# LCD_Camera_Connectors.net
KiCad netlist of a schematic drawn in Altium Designer
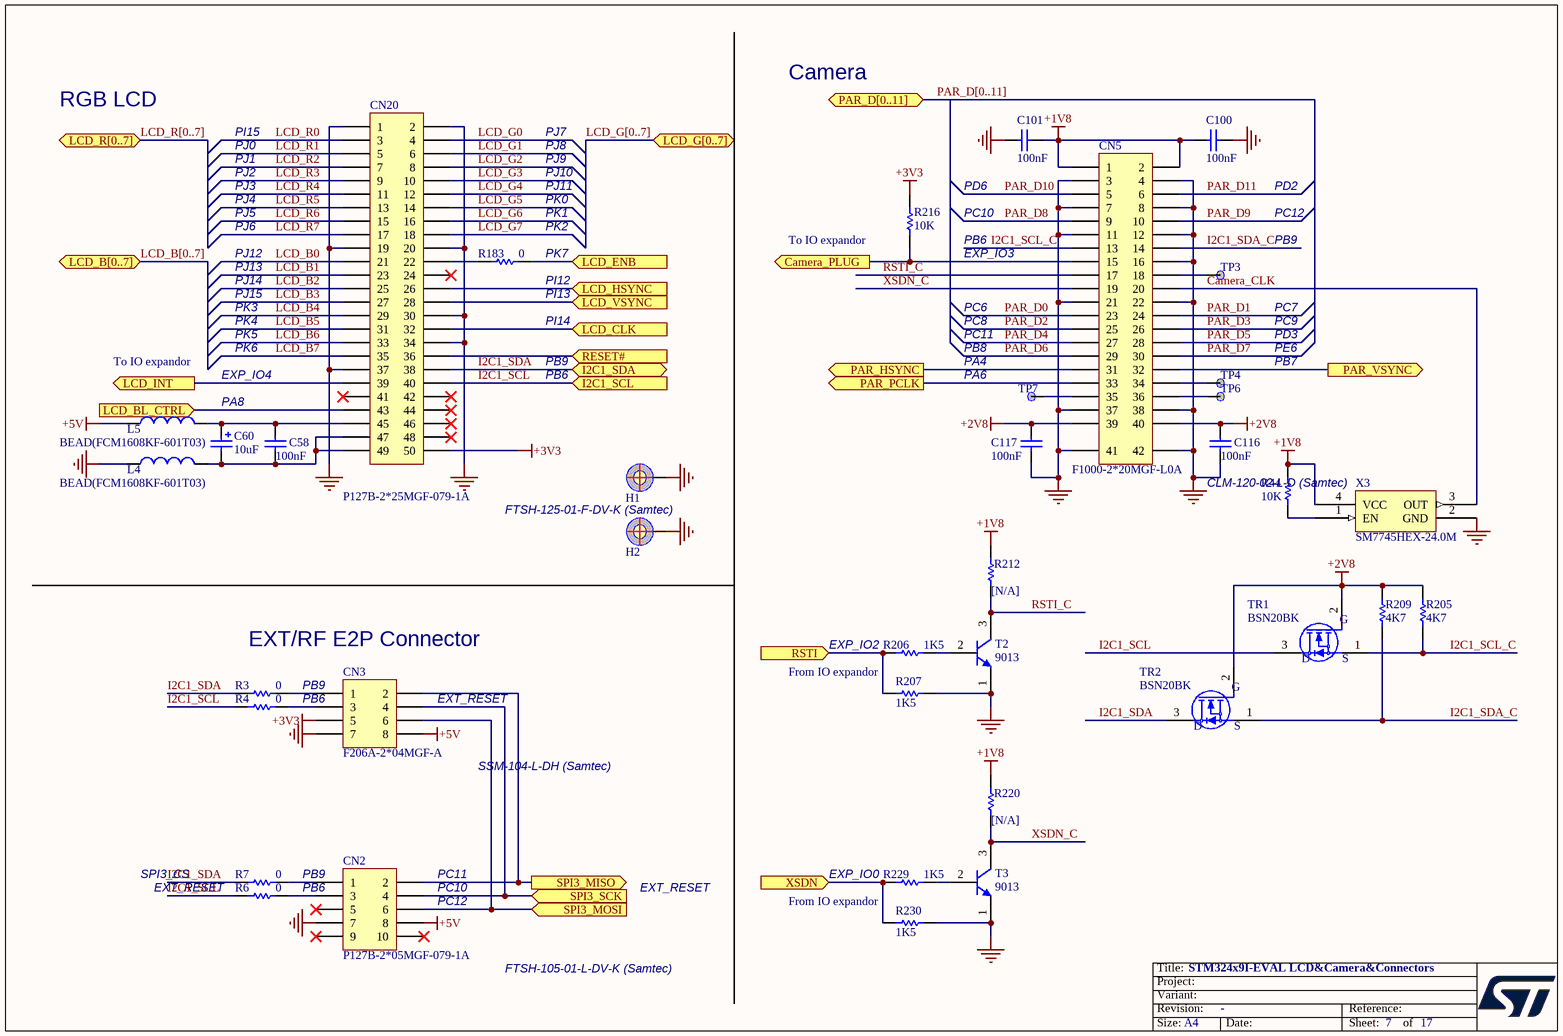
[diagram p0: LCD&Camera&Connectors.SchDoc]

(export (version "E")
  (design (tool "Eeschema 10.0.6"))
  (components
    (comp (ref "C58")
      (value "100nF")
      (footprint "0603C")
      (description "Capacitor")
      (fields (field (name "PUBLISHER") "Altium Limited"))
      (libsource (lib "Miscellaneous Devices") (part "Cap"))
    )
    (comp (ref "C60")
      (value "10uF")
      (footprint "TAN-A")
      (description "Polarized Capacitor (Radial)")
      (fields (field (name "PUBLISHER") "Altium Limited"))
      (libsource (lib "Miscellaneous Devices") (part "Cap Pol1"))
    )
    (comp (ref "C100")
      (value "100nF")
      (footprint "0603C")
      (description "Capacitor")
      (fields (field (name "PUBLISHER") "Altium Limited"))
      (libsource (lib "Miscellaneous Devices") (part "Cap"))
    )
    (comp (ref "C101")
      (value "100nF")
      (footprint "0603C")
      (description "Capacitor")
      (fields (field (name "PUBLISHER") "Altium Limited"))
      (libsource (lib "Miscellaneous Devices") (part "Cap"))
    )
    (comp (ref "C116")
      (value "100nF")
      (footprint "0603C")
      (description "Capacitor")
      (fields (field (name "PUBLISHER") "Altium Limited"))
      (libsource (lib "Miscellaneous Devices") (part "Cap"))
    )
    (comp (ref "C117")
      (value "100nF")
      (footprint "0603C")
      (description "Capacitor")
      (fields (field (name "PUBLISHER") "Altium Limited"))
      (libsource (lib "Miscellaneous Devices") (part "Cap"))
    )
    (comp (ref "CN2")
      (value "P127B-2*05MGF-079-1A")
      (footprint "FTSH-105-01-L-DV-K")
      (description "Header, 5-Pin, Dual row")
      (fields (field (name "PUBLISHER") "Altium Limited"))
      (libsource (lib "mb1045") (part "FTSH-15-01-L-DV-ES-K"))
    )
    (comp (ref "CN3")
      (value "F206A-2*04MGF-A")
      (footprint "SSM-104-L-DH")
      (description "Header, 5-Pin, Dual row")
      (fields (field (name "PUBLISHER") "Altium Limited"))
      (libsource (lib "mb1045") (part "SSM-104-L-DH"))
    )
    (comp (ref "CN5")
      (value "F1000-2*20MGF-L0A")
      (footprint "CLM-120-02-L-D")
      (description "Header, 20-Pin, Dual row")
      (fields (field (name "PUBLISHER") "Altium Limited"))
      (libsource (lib "mb1045") (part "CLM-120-02-L-D"))
    )
    (comp (ref "CN20")
      (value "P127B-2*25MGF-079-1A")
      (footprint "FTSH-125-01-F-DV")
      (description "Header, 26-Pin, Dual row")
      (fields (field (name "PUBLISHER") "Altium Limited"))
      (libsource (lib "mb1045") (part "Header 25X2"))
    )
    (comp (ref "H1")
      (value "POSITION HOLE")
      (footprint "HOLE_C9D4R5")
      (libsource (lib "mb1045") (part "POSITION HOLE"))
    )
    (comp (ref "H2")
      (value "POSITION HOLE")
      (footprint "HOLE_C9D4R5")
      (libsource (lib "mb1045") (part "POSITION HOLE"))
    )
    (comp (ref "L4")
      (value "BEAD(FCM1608KF-601T03)")
      (footprint "0603L")
      (description "Inductor")
      (fields (field (name "PUBLISHER") "Altium Limited"))
      (libsource (lib "Miscellaneous Devices") (part "Inductor"))
    )
    (comp (ref "L5")
      (value "BEAD(FCM1608KF-601T03)")
      (footprint "0603L")
      (description "Inductor")
      (fields (field (name "PUBLISHER") "Altium Limited"))
      (libsource (lib "Miscellaneous Devices") (part "Inductor"))
    )
    (comp (ref "R3")
      (value "0")
      (footprint "0603R")
      (description "Resistor")
      (fields (field (name "PUBLISHER") "Altium Limited"))
      (libsource (lib "Miscellaneous Devices") (part "Res1"))
    )
    (comp (ref "R4")
      (value "0")
      (footprint "0603R")
      (description "Resistor")
      (fields (field (name "PUBLISHER") "Altium Limited"))
      (libsource (lib "Miscellaneous Devices") (part "Res1"))
    )
    (comp (ref "R6")
      (value "0")
      (footprint "0603R")
      (description "Resistor")
      (fields (field (name "PUBLISHER") "Altium Limited"))
      (libsource (lib "Miscellaneous Devices") (part "Res1"))
    )
    (comp (ref "R7")
      (value "0")
      (footprint "0603R")
      (description "Resistor")
      (fields (field (name "PUBLISHER") "Altium Limited"))
      (libsource (lib "Miscellaneous Devices") (part "Res1"))
    )
    (comp (ref "R44")
      (value "10K")
      (footprint "0402R")
      (description "Resistor")
      (fields (field (name "PUBLISHER") "Altium Limited"))
      (libsource (lib "Miscellaneous Devices") (part "Res1"))
    )
    (comp (ref "R183")
      (value "0")
      (footprint "0603R")
      (description "Resistor")
      (fields (field (name "PUBLISHER") "Altium Limited"))
      (libsource (lib "Miscellaneous Devices") (part "Res1"))
    )
    (comp (ref "R205")
      (value "4K7")
      (footprint "0603R")
      (description "Resistor")
      (fields (field (name "PUBLISHER") "Altium Limited"))
      (libsource (lib "Miscellaneous Devices") (part "res1"))
    )
    (comp (ref "R206")
      (value "1K5")
      (footprint "0603R")
      (description "Resistor")
      (fields (field (name "PUBLISHER") "Altium Limited"))
      (libsource (lib "Miscellaneous Devices") (part "Res1"))
    )
    (comp (ref "R207")
      (value "1K5")
      (footprint "0603R")
      (description "Resistor")
      (fields (field (name "PUBLISHER") "Altium Limited"))
      (libsource (lib "Miscellaneous Devices") (part "Res1"))
    )
    (comp (ref "R209")
      (value "4K7")
      (footprint "0603R")
      (description "Resistor")
      (fields (field (name "PUBLISHER") "Altium Limited"))
      (libsource (lib "Miscellaneous Devices") (part "res1"))
    )
    (comp (ref "R212")
      (value "[N/A]")
      (footprint "0603R")
      (description "Resistor")
      (fields (field (name "PUBLISHER") "Altium Limited"))
      (libsource (lib "Miscellaneous Devices") (part "res1"))
    )
    (comp (ref "R216")
      (value "10K")
      (footprint "0603R")
      (description "Resistor")
      (fields (field (name "PUBLISHER") "Altium Limited"))
      (libsource (lib "Miscellaneous Devices") (part "Res1"))
    )
    (comp (ref "R220")
      (value "[N/A]")
      (footprint "0603R")
      (description "Resistor")
      (fields (field (name "PUBLISHER") "Altium Limited"))
      (libsource (lib "Miscellaneous Devices") (part "res1"))
    )
    (comp (ref "R229")
      (value "1K5")
      (footprint "0603R")
      (description "Resistor")
      (fields (field (name "PUBLISHER") "Altium Limited"))
      (libsource (lib "Miscellaneous Devices") (part "Res1"))
    )
    (comp (ref "R230")
      (value "1K5")
      (footprint "0603R")
      (description "Resistor")
      (fields (field (name "PUBLISHER") "Altium Limited"))
      (libsource (lib "Miscellaneous Devices") (part "Res1"))
    )
    (comp (ref "T2")
      (value "9013")
      (footprint "SOT23-213")
      (description "NPN Bipolar Transistor")
      (fields (field (name "PUBLISHER") "Altium Limited"))
      (libsource (lib "mb1045") (part "NPN"))
    )
    (comp (ref "T3")
      (value "9013")
      (footprint "SOT23-213")
      (description "NPN Bipolar Transistor")
      (fields (field (name "PUBLISHER") "Altium Limited"))
      (libsource (lib "mb1045") (part "NPN"))
    )
    (comp (ref "TP3") (value "~") (footprint "TP") (libsource (lib "*") (part "TP")))
    (comp (ref "TP4") (value "~") (footprint "TP") (libsource (lib "*") (part "TP")))
    (comp (ref "TP6") (value "~") (footprint "TP") (libsource (lib "*") (part "TP")))
    (comp (ref "TP7") (value "~") (footprint "TP") (libsource (lib "*") (part "TP")))
    (comp (ref "TR1")
      (value "BSN20BK")
      (footprint "SOT23-213")
      (description "Transistor, N-channel enhancement mode field-effect transistor")
      (libsource (lib "MB525") (part "2N7000"))
    )
    (comp (ref "TR2")
      (value "BSN20BK")
      (footprint "SOT23-213")
      (description "Transistor, N-channel enhancement mode field-effect transistor")
      (libsource (lib "MB525") (part "2N7000"))
    )
    (comp (ref "X3")
      (value "SM7745HEX-24.0M")
      (footprint "OSC_4SM_7X5")
      (libsource (lib "MB784") (part "SM7745HEV-50.0M"))
    )
  )
  (nets
    (net (code "1") (name "+1V8") (class "Default")
      (node (ref "C100") (pin "1") (pinfunction "1_1") (pintype "passive"))
      (node (ref "C101") (pin "2") (pinfunction "2_2") (pintype "passive"))
      (node (ref "CN5") (pin "1") (pinfunction "1_1") (pintype "passive"))
      (node (ref "CN5") (pin "2") (pinfunction "2_2") (pintype "passive"))
      (node (ref "R212") (pin "2") (pinfunction "2_2") (pintype "passive"))
      (node (ref "R220") (pin "2") (pinfunction "2_2") (pintype "passive"))
      (node (ref "R44") (pin "2") (pinfunction "2_2") (pintype "passive"))
      (node (ref "X3") (pin "4") (pinfunction "VCC_4") (pintype "passive"))
    )
    (net (code "2") (name "+2V8") (class "Default")
      (node (ref "C116") (pin "1") (pinfunction "1_1") (pintype "passive"))
      (node (ref "C117") (pin "1") (pinfunction "1_1") (pintype "passive"))
      (node (ref "CN5") (pin "39") (pinfunction "39_39") (pintype "passive"))
      (node (ref "CN5") (pin "40") (pinfunction "40_40") (pintype "passive"))
      (node (ref "R205") (pin "2") (pinfunction "2_2") (pintype "passive"))
      (node (ref "R209") (pin "2") (pinfunction "2_2") (pintype "passive"))
      (node (ref "TR1") (pin "2") (pinfunction "G_2") (pintype "passive"))
      (node (ref "TR2") (pin "2") (pinfunction "G_2") (pintype "passive"))
    )
    (net (code "3") (name "+3V3") (class "Default")
      (node (ref "CN20") (pin "50") (pinfunction "50_50") (pintype "passive"))
      (node (ref "CN3") (pin "5") (pinfunction "5_5") (pintype "passive"))
      (node (ref "R216") (pin "1") (pinfunction "1_1") (pintype "passive"))
    )
    (net (code "4") (name "+5V") (class "Default")
      (node (ref "CN2") (pin "8") (pinfunction "8_8") (pintype "passive"))
      (node (ref "CN3") (pin "8") (pinfunction "8_8") (pintype "passive"))
      (node (ref "L5") (pin "1") (pinfunction "1_1") (pintype "passive"))
    )
    (net (code "5") (name "/Camera_CLK") (class "Default")
      (node (ref "CN5") (pin "20") (pinfunction "20_20") (pintype "passive"))
      (node (ref "X3") (pin "3") (pinfunction "OUT_3") (pintype "output"))
    )
    (net (code "6") (name "/Camera_PLUG") (class "Default")
      (node (ref "CN5") (pin "15") (pinfunction "15_15") (pintype "passive"))
      (node (ref "R216") (pin "2") (pinfunction "2_2") (pintype "passive"))
    )
    (net (code "7") (name "/I2C1_SCL") (class "Default")
      (node (ref "CN20") (pin "40") (pinfunction "40_40") (pintype "passive"))
      (node (ref "R4") (pin "1") (pinfunction "1_1") (pintype "passive"))
      (node (ref "R6") (pin "1") (pinfunction "1_1") (pintype "passive"))
      (node (ref "TR1") (pin "3") (pinfunction "D_3") (pintype "passive"))
    )
    (net (code "8") (name "/I2C1_SCL_C") (class "Default")
      (node (ref "CN5") (pin "13") (pinfunction "13_13") (pintype "passive"))
      (node (ref "R205") (pin "1") (pinfunction "1_1") (pintype "passive"))
      (node (ref "TR1") (pin "1") (pinfunction "S_1") (pintype "passive"))
    )
    (net (code "9") (name "/I2C1_SDA") (class "Default")
      (node (ref "CN20") (pin "38") (pinfunction "38_38") (pintype "passive"))
      (node (ref "R3") (pin "1") (pinfunction "1_1") (pintype "passive"))
      (node (ref "R7") (pin "1") (pinfunction "1_1") (pintype "passive"))
      (node (ref "TR2") (pin "3") (pinfunction "D_3") (pintype "passive"))
    )
    (net (code "10") (name "/I2C1_SDA_C") (class "Default")
      (node (ref "CN5") (pin "14") (pinfunction "14_14") (pintype "passive"))
      (node (ref "R209") (pin "1") (pinfunction "1_1") (pintype "passive"))
      (node (ref "TR2") (pin "1") (pinfunction "S_1") (pintype "passive"))
    )
    (net (code "11") (name "/LCD_B0") (class "Default")
      (node (ref "CN20") (pin "21") (pinfunction "21_21") (pintype "passive"))
    )
    (net (code "12") (name "/LCD_B1") (class "Default")
      (node (ref "CN20") (pin "23") (pinfunction "23_23") (pintype "passive"))
    )
    (net (code "13") (name "/LCD_B2") (class "Default")
      (node (ref "CN20") (pin "25") (pinfunction "25_25") (pintype "passive"))
    )
    (net (code "14") (name "/LCD_B3") (class "Default")
      (node (ref "CN20") (pin "27") (pinfunction "27_27") (pintype "passive"))
    )
    (net (code "15") (name "/LCD_B4") (class "Default")
      (node (ref "CN20") (pin "29") (pinfunction "29_29") (pintype "passive"))
    )
    (net (code "16") (name "/LCD_B5") (class "Default")
      (node (ref "CN20") (pin "31") (pinfunction "31_31") (pintype "passive"))
    )
    (net (code "17") (name "/LCD_B6") (class "Default")
      (node (ref "CN20") (pin "33") (pinfunction "33_33") (pintype "passive"))
    )
    (net (code "18") (name "/LCD_B7") (class "Default")
      (node (ref "CN20") (pin "35") (pinfunction "35_35") (pintype "passive"))
    )
    (net (code "19") (name "/LCD_BL_CTRL") (class "Default")
      (node (ref "CN20") (pin "43") (pinfunction "43_43") (pintype "passive"))
    )
    (net (code "21") (name "/LCD_CLK") (class "Default")
      (node (ref "CN20") (pin "32") (pinfunction "32_32") (pintype "passive"))
    )
    (net (code "22") (name "/LCD_ENB") (class "Default")
      (node (ref "R183") (pin "2") (pinfunction "2_2") (pintype "passive"))
    )
    (net (code "23") (name "/LCD_G0") (class "Default")
      (node (ref "CN20") (pin "4") (pinfunction "4_4") (pintype "passive"))
    )
    (net (code "24") (name "/LCD_G1") (class "Default")
      (node (ref "CN20") (pin "6") (pinfunction "6_6") (pintype "passive"))
    )
    (net (code "25") (name "/LCD_G2") (class "Default")
      (node (ref "CN20") (pin "8") (pinfunction "8_8") (pintype "passive"))
    )
    (net (code "26") (name "/LCD_G3") (class "Default")
      (node (ref "CN20") (pin "10") (pinfunction "10_10") (pintype "passive"))
    )
    (net (code "27") (name "/LCD_G4") (class "Default")
      (node (ref "CN20") (pin "12") (pinfunction "12_12") (pintype "passive"))
    )
    (net (code "28") (name "/LCD_G5") (class "Default")
      (node (ref "CN20") (pin "14") (pinfunction "14_14") (pintype "passive"))
    )
    (net (code "29") (name "/LCD_G6") (class "Default")
      (node (ref "CN20") (pin "16") (pinfunction "16_16") (pintype "passive"))
    )
    (net (code "30") (name "/LCD_G7") (class "Default")
      (node (ref "CN20") (pin "18") (pinfunction "18_18") (pintype "passive"))
    )
    (net (code "32") (name "/LCD_HSYNC") (class "Default")
      (node (ref "CN20") (pin "26") (pinfunction "26_26") (pintype "passive"))
    )
    (net (code "33") (name "/LCD_INT") (class "Default")
      (node (ref "CN20") (pin "39") (pinfunction "39_39") (pintype "passive"))
    )
    (net (code "34") (name "/LCD_R0") (class "Default")
      (node (ref "CN20") (pin "3") (pinfunction "3_3") (pintype "passive"))
    )
    (net (code "35") (name "/LCD_R1") (class "Default")
      (node (ref "CN20") (pin "5") (pinfunction "5_5") (pintype "passive"))
    )
    (net (code "36") (name "/LCD_R2") (class "Default")
      (node (ref "CN20") (pin "7") (pinfunction "7_7") (pintype "passive"))
    )
    (net (code "37") (name "/LCD_R3") (class "Default")
      (node (ref "CN20") (pin "9") (pinfunction "9_9") (pintype "passive"))
    )
    (net (code "38") (name "/LCD_R4") (class "Default")
      (node (ref "CN20") (pin "11") (pinfunction "11_11") (pintype "passive"))
    )
    (net (code "39") (name "/LCD_R5") (class "Default")
      (node (ref "CN20") (pin "13") (pinfunction "13_13") (pintype "passive"))
    )
    (net (code "40") (name "/LCD_R6") (class "Default")
      (node (ref "CN20") (pin "15") (pinfunction "15_15") (pintype "passive"))
    )
    (net (code "41") (name "/LCD_R7") (class "Default")
      (node (ref "CN20") (pin "17") (pinfunction "17_17") (pintype "passive"))
    )
    (net (code "43") (name "/LCD_VSYNC") (class "Default")
      (node (ref "CN20") (pin "28") (pinfunction "28_28") (pintype "passive"))
    )
    (net (code "44") (name "/PAR_D0") (class "Default")
      (node (ref "CN5") (pin "23") (pinfunction "23_23") (pintype "passive"))
    )
    (net (code "45") (name "/PAR_D1") (class "Default")
      (node (ref "CN5") (pin "24") (pinfunction "24_24") (pintype "passive"))
    )
    (net (code "46") (name "/PAR_D2") (class "Default")
      (node (ref "CN5") (pin "25") (pinfunction "25_25") (pintype "passive"))
    )
    (net (code "47") (name "/PAR_D3") (class "Default")
      (node (ref "CN5") (pin "26") (pinfunction "26_26") (pintype "passive"))
    )
    (net (code "48") (name "/PAR_D4") (class "Default")
      (node (ref "CN5") (pin "27") (pinfunction "27_27") (pintype "passive"))
    )
    (net (code "49") (name "/PAR_D5") (class "Default")
      (node (ref "CN5") (pin "28") (pinfunction "28_28") (pintype "passive"))
    )
    (net (code "50") (name "/PAR_D6") (class "Default")
      (node (ref "CN5") (pin "29") (pinfunction "29_29") (pintype "passive"))
    )
    (net (code "51") (name "/PAR_D7") (class "Default")
      (node (ref "CN5") (pin "30") (pinfunction "30_30") (pintype "passive"))
    )
    (net (code "52") (name "/PAR_D8") (class "Default")
      (node (ref "CN5") (pin "9") (pinfunction "9_9") (pintype "passive"))
    )
    (net (code "53") (name "/PAR_D9") (class "Default")
      (node (ref "CN5") (pin "10") (pinfunction "10_10") (pintype "passive"))
    )
    (net (code "54") (name "/PAR_D10") (class "Default")
      (node (ref "CN5") (pin "5") (pinfunction "5_5") (pintype "passive"))
    )
    (net (code "55") (name "/PAR_D11") (class "Default")
      (node (ref "CN5") (pin "6") (pinfunction "6_6") (pintype "passive"))
    )
    (net (code "57") (name "/PAR_HSYNC") (class "Default")
      (node (ref "CN5") (pin "31") (pinfunction "31_31") (pintype "passive"))
    )
    (net (code "58") (name "/PAR_PCLK") (class "Default")
      (node (ref "CN5") (pin "33") (pinfunction "33_33") (pintype "passive"))
    )
    (net (code "59") (name "/PAR_VSYNC") (class "Default")
      (node (ref "CN5") (pin "32") (pinfunction "32_32") (pintype "passive"))
    )
    (net (code "60") (name "/RESET#") (class "Default")
      (node (ref "CN20") (pin "36") (pinfunction "36_36") (pintype "passive"))
    )
    (net (code "61") (name "/RSTI") (class "Default")
      (node (ref "R206") (pin "2") (pinfunction "2_2") (pintype "passive"))
      (node (ref "R207") (pin "1") (pinfunction "1_1") (pintype "passive"))
    )
    (net (code "62") (name "/RSTI_C") (class "Default")
      (node (ref "CN5") (pin "17") (pinfunction "17_17") (pintype "passive"))
      (node (ref "R212") (pin "1") (pinfunction "1_1") (pintype "passive"))
      (node (ref "T2") (pin "3") (pinfunction "C_3") (pintype "passive"))
    )
    (net (code "63") (name "/SPI3_MISO") (class "Default")
      (node (ref "CN2") (pin "2") (pinfunction "2_2") (pintype "passive"))
      (node (ref "CN3") (pin "2") (pinfunction "2_2") (pintype "passive"))
    )
    (net (code "64") (name "/SPI3_MOSI") (class "Default")
      (node (ref "CN2") (pin "6") (pinfunction "6_6") (pintype "passive"))
      (node (ref "CN3") (pin "6") (pinfunction "6_6") (pintype "passive"))
    )
    (net (code "65") (name "/SPI3_SCK") (class "Default")
      (node (ref "CN2") (pin "4") (pinfunction "4_4") (pintype "passive"))
      (node (ref "CN3") (pin "4") (pinfunction "4_4") (pintype "passive"))
    )
    (net (code "66") (name "/XSDN") (class "Default")
      (node (ref "R229") (pin "2") (pinfunction "2_2") (pintype "passive"))
      (node (ref "R230") (pin "1") (pinfunction "1_1") (pintype "passive"))
    )
    (net (code "67") (name "/XSDN_C") (class "Default")
      (node (ref "CN5") (pin "19") (pinfunction "19_19") (pintype "passive"))
      (node (ref "R220") (pin "1") (pinfunction "1_1") (pintype "passive"))
      (node (ref "T3") (pin "3") (pinfunction "C_3") (pintype "passive"))
    )
    (net (code "68") (name "GND") (class "Default")
      (node (ref "C100") (pin "2") (pinfunction "2_2") (pintype "passive"))
      (node (ref "C101") (pin "1") (pinfunction "1_1") (pintype "passive"))
      (node (ref "C116") (pin "2") (pinfunction "2_2") (pintype "passive"))
      (node (ref "C117") (pin "2") (pinfunction "2_2") (pintype "passive"))
      (node (ref "CN2") (pin "7") (pinfunction "7_7") (pintype "passive"))
      (node (ref "CN20") (pin "1") (pinfunction "1_1") (pintype "passive"))
      (node (ref "CN20") (pin "19") (pinfunction "19_19") (pintype "passive"))
      (node (ref "CN20") (pin "2") (pinfunction "2_2") (pintype "passive"))
      (node (ref "CN20") (pin "20") (pinfunction "20_20") (pintype "passive"))
      (node (ref "CN20") (pin "30") (pinfunction "30_30") (pintype "passive"))
      (node (ref "CN20") (pin "34") (pinfunction "34_34") (pintype "passive"))
      (node (ref "CN20") (pin "37") (pinfunction "37_37") (pintype "passive"))
      (node (ref "CN3") (pin "7") (pinfunction "7_7") (pintype "passive"))
      (node (ref "CN5") (pin "11") (pinfunction "11_11") (pintype "passive"))
      (node (ref "CN5") (pin "12") (pinfunction "12_12") (pintype "passive"))
      (node (ref "CN5") (pin "16") (pinfunction "16_16") (pintype "passive"))
      (node (ref "CN5") (pin "21") (pinfunction "21_21") (pintype "passive"))
      (node (ref "CN5") (pin "22") (pinfunction "22_22") (pintype "passive"))
      (node (ref "CN5") (pin "3") (pinfunction "3_3") (pintype "passive"))
      (node (ref "CN5") (pin "37") (pinfunction "37_37") (pintype "passive"))
      (node (ref "CN5") (pin "38") (pinfunction "38_38") (pintype "passive"))
      (node (ref "CN5") (pin "4") (pinfunction "4_4") (pintype "passive"))
      (node (ref "CN5") (pin "41") (pinfunction "41_41") (pintype "passive"))
      (node (ref "CN5") (pin "42") (pinfunction "42_42") (pintype "passive"))
      (node (ref "CN5") (pin "7") (pinfunction "7_7") (pintype "passive"))
      (node (ref "CN5") (pin "8") (pinfunction "8_8") (pintype "passive"))
      (node (ref "H1") (pin "1") (pinfunction "1_1") (pintype "passive"))
      (node (ref "H2") (pin "1") (pinfunction "1_1") (pintype "passive"))
      (node (ref "L4") (pin "1") (pinfunction "1_1") (pintype "passive"))
      (node (ref "R207") (pin "2") (pinfunction "2_2") (pintype "passive"))
      (node (ref "R230") (pin "2") (pinfunction "2_2") (pintype "passive"))
      (node (ref "T2") (pin "1") (pinfunction "E_1") (pintype "passive"))
      (node (ref "T3") (pin "1") (pinfunction "E_1") (pintype "passive"))
      (node (ref "X3") (pin "2") (pinfunction "GND_2") (pintype "passive"))
    )
    (net (code "69") (name "Net-(C58-Pad1)") (class "Default")
      (node (ref "C58") (pin "1") (pinfunction "1_1") (pintype "passive"))
      (node (ref "C60") (pin "1") (pinfunction "1_1") (pintype "passive"))
      (node (ref "CN20") (pin "45") (pinfunction "45_45") (pintype "passive"))
      (node (ref "L5") (pin "2") (pinfunction "2_2") (pintype "passive"))
    )
    (net (code "70") (name "Net-(C58-Pad2)") (class "Default")
      (node (ref "C58") (pin "2") (pinfunction "2_2") (pintype "passive"))
      (node (ref "C60") (pin "2") (pinfunction "2_2") (pintype "passive"))
      (node (ref "CN20") (pin "47") (pinfunction "47_47") (pintype "passive"))
      (node (ref "CN20") (pin "49") (pinfunction "49_49") (pintype "passive"))
      (node (ref "L4") (pin "2") (pinfunction "2_2") (pintype "passive"))
    )
    (net (code "71") (name "Net-(CN2-Pad1)") (class "Default")
      (node (ref "CN2") (pin "1") (pinfunction "1_1") (pintype "passive"))
      (node (ref "R7") (pin "2") (pinfunction "2_2") (pintype "passive"))
    )
    (net (code "72") (name "Net-(CN2-Pad3)") (class "Default")
      (node (ref "CN2") (pin "3") (pinfunction "3_3") (pintype "passive"))
      (node (ref "R6") (pin "2") (pinfunction "2_2") (pintype "passive"))
    )
    (net (code "73") (name "Net-(CN3-Pad1)") (class "Default")
      (node (ref "CN3") (pin "1") (pinfunction "1_1") (pintype "passive"))
      (node (ref "R3") (pin "2") (pinfunction "2_2") (pintype "passive"))
    )
    (net (code "74") (name "Net-(CN3-Pad3)") (class "Default")
      (node (ref "CN3") (pin "3") (pinfunction "3_3") (pintype "passive"))
      (node (ref "R4") (pin "2") (pinfunction "2_2") (pintype "passive"))
    )
    (net (code "75") (name "Net-(CN5-Pad18)") (class "Default")
      (node (ref "CN5") (pin "18") (pinfunction "18_18") (pintype "passive"))
      (node (ref "TP3") (pin "1") (pinfunction "1_1") (pintype "passive"))
    )
    (net (code "76") (name "Net-(CN5-Pad34)") (class "Default")
      (node (ref "CN5") (pin "34") (pinfunction "34_34") (pintype "passive"))
      (node (ref "TP4") (pin "1") (pinfunction "1_1") (pintype "passive"))
    )
    (net (code "77") (name "Net-(CN5-Pad35)") (class "Default")
      (node (ref "CN5") (pin "35") (pinfunction "35_35") (pintype "passive"))
      (node (ref "TP7") (pin "1") (pinfunction "1_1") (pintype "passive"))
    )
    (net (code "78") (name "Net-(CN5-Pad36)") (class "Default")
      (node (ref "CN5") (pin "36") (pinfunction "36_36") (pintype "passive"))
      (node (ref "TP6") (pin "1") (pinfunction "1_1") (pintype "passive"))
    )
    (net (code "79") (name "Net-(CN20-Pad22)") (class "Default")
      (node (ref "CN20") (pin "22") (pinfunction "22_22") (pintype "passive"))
      (node (ref "R183") (pin "1") (pinfunction "1_1") (pintype "passive"))
    )
    (net (code "80") (name "Net-(T2-B)") (class "Default")
      (node (ref "R206") (pin "1") (pinfunction "1_1") (pintype "passive"))
      (node (ref "T2") (pin "2") (pinfunction "B_2") (pintype "passive"))
    )
    (net (code "81") (name "Net-(T3-B)") (class "Default")
      (node (ref "R229") (pin "1") (pinfunction "1_1") (pintype "passive"))
      (node (ref "T3") (pin "2") (pinfunction "B_2") (pintype "passive"))
    )
    (net (code "82") (name "Net-(X3-EN)") (class "Default")
      (node (ref "R44") (pin "1") (pinfunction "1_1") (pintype "passive"))
      (node (ref "X3") (pin "1") (pinfunction "EN_1") (pintype "input"))
    )
    (net (code "83") (name "unconnected-(CN2-Pad5)") (class "Default")
      (node (ref "CN2") (pin "5") (pinfunction "5_5") (pintype "passive+no_connect"))
    )
    (net (code "84") (name "unconnected-(CN2-Pad9)") (class "Default")
      (node (ref "CN2") (pin "9") (pinfunction "9_9") (pintype "passive+no_connect"))
    )
    (net (code "85") (name "unconnected-(CN2-Pad10)") (class "Default")
      (node (ref "CN2") (pin "10") (pinfunction "10_10") (pintype "passive+no_connect"))
    )
    (net (code "86") (name "unconnected-(CN20-Pad24)") (class "Default")
      (node (ref "CN20") (pin "24") (pinfunction "24_24") (pintype "passive+no_connect"))
    )
    (net (code "87") (name "unconnected-(CN20-Pad41)") (class "Default")
      (node (ref "CN20") (pin "41") (pinfunction "41_41") (pintype "passive+no_connect"))
    )
    (net (code "88") (name "unconnected-(CN20-Pad42)") (class "Default")
      (node (ref "CN20") (pin "42") (pinfunction "42_42") (pintype "passive+no_connect"))
    )
    (net (code "89") (name "unconnected-(CN20-Pad44)") (class "Default")
      (node (ref "CN20") (pin "44") (pinfunction "44_44") (pintype "passive+no_connect"))
    )
    (net (code "90") (name "unconnected-(CN20-Pad46)") (class "Default")
      (node (ref "CN20") (pin "46") (pinfunction "46_46") (pintype "passive+no_connect"))
    )
    (net (code "91") (name "unconnected-(CN20-Pad48)") (class "Default")
      (node (ref "CN20") (pin "48") (pinfunction "48_48") (pintype "passive+no_connect"))
    )
  )
)
